# SCH_I2C_Divider_2021-08-28.net
KiCad netlist of a schematic drawn in EasyEDA
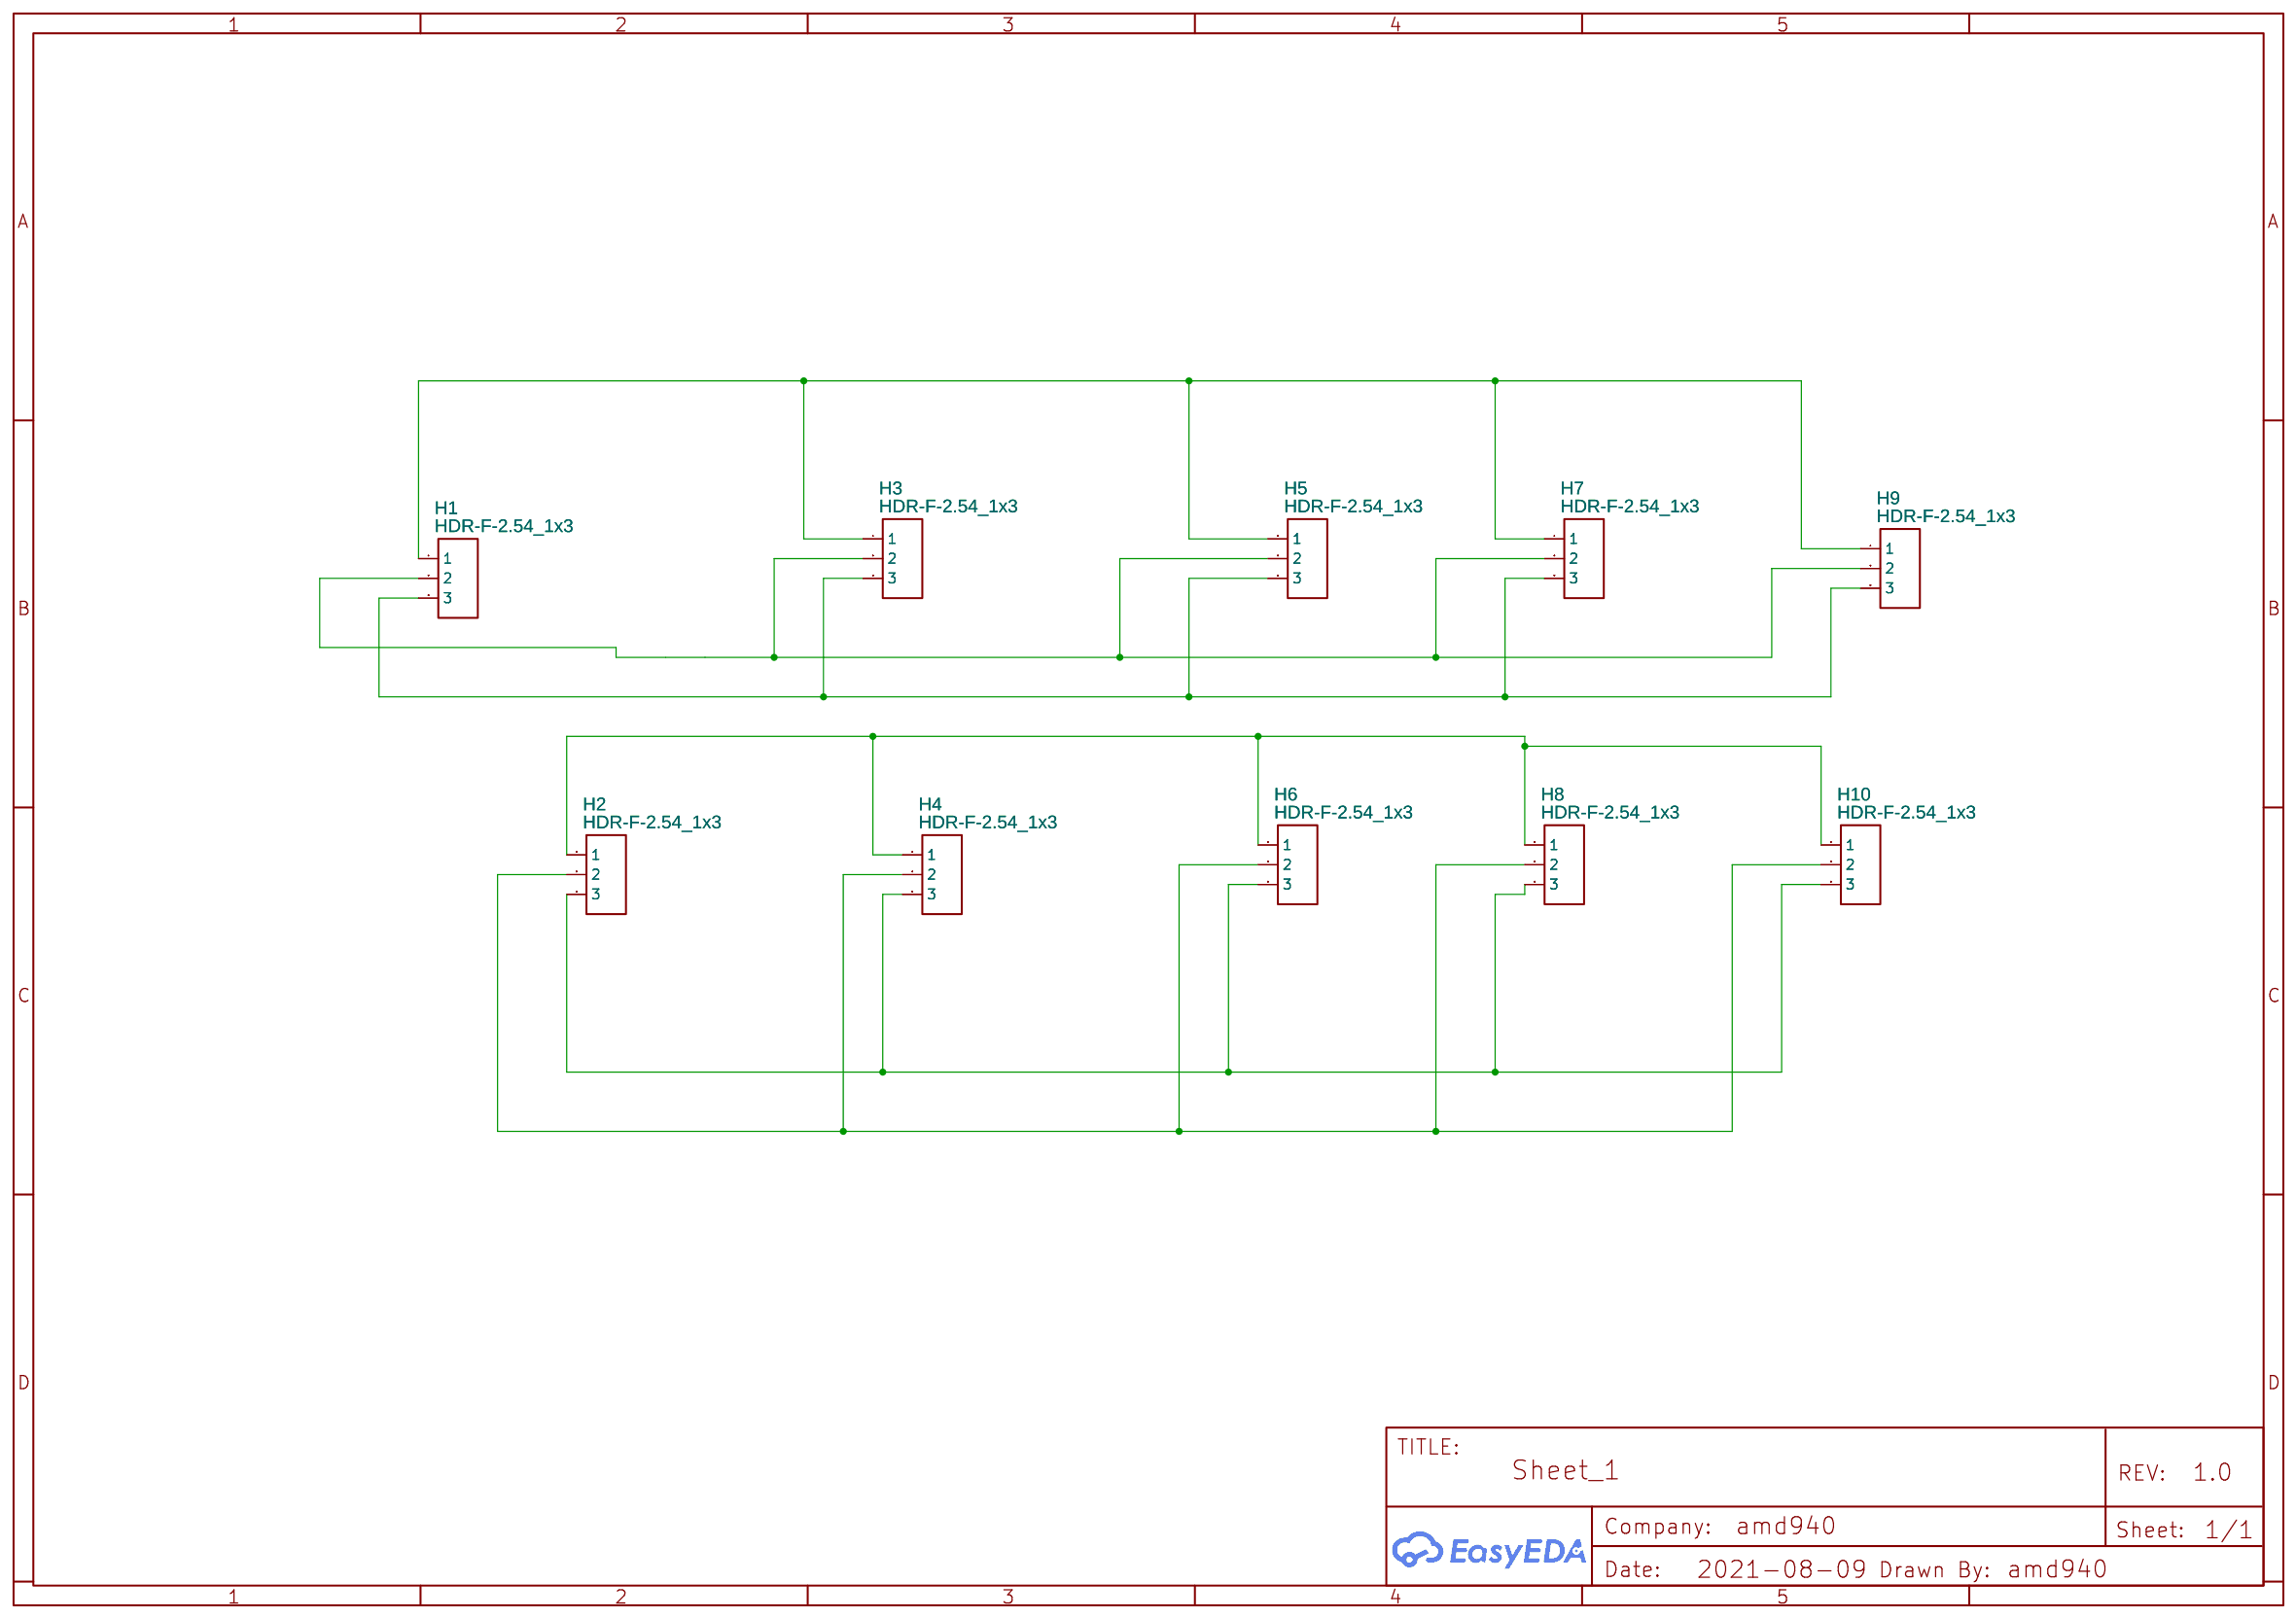
[diagram p0: schematic sheet]

(export (version "E")
  (design (tool "Eeschema 10.0.6"))
  (components
    (comp (ref "H1")
      (value "HDR-F-2.54_1x3")
      (fields (field (name "BOM_Supplier Part") "C146690"))
      (libsource (lib "") (part "HDR-F-2.54_1x3"))
    )
    (comp (ref "H2")
      (value "HDR-F-2.54_1x3")
      (fields (field (name "BOM_Supplier Part") "C146690"))
      (libsource (lib "") (part "HDR-F-2.54_1x3"))
    )
    (comp (ref "H3")
      (value "HDR-F-2.54_1x3")
      (fields (field (name "BOM_Supplier Part") "C146690"))
      (libsource (lib "") (part "HDR-F-2.54_1x3"))
    )
    (comp (ref "H4")
      (value "HDR-F-2.54_1x3")
      (fields (field (name "BOM_Supplier Part") "C146690"))
      (libsource (lib "") (part "HDR-F-2.54_1x3"))
    )
    (comp (ref "H5")
      (value "HDR-F-2.54_1x3")
      (fields (field (name "BOM_Supplier Part") "C146690"))
      (libsource (lib "") (part "HDR-F-2.54_1x3"))
    )
    (comp (ref "H6")
      (value "HDR-F-2.54_1x3")
      (fields (field (name "BOM_Supplier Part") "C146690"))
      (libsource (lib "") (part "HDR-F-2.54_1x3"))
    )
    (comp (ref "H7")
      (value "HDR-F-2.54_1x3")
      (fields (field (name "BOM_Supplier Part") "C146690"))
      (libsource (lib "") (part "HDR-F-2.54_1x3"))
    )
    (comp (ref "H8")
      (value "HDR-F-2.54_1x3")
      (fields (field (name "BOM_Supplier Part") "C146690"))
      (libsource (lib "") (part "HDR-F-2.54_1x3"))
    )
    (comp (ref "H9")
      (value "HDR-F-2.54_1x3")
      (fields (field (name "BOM_Supplier Part") "C146690"))
      (libsource (lib "") (part "HDR-F-2.54_1x3"))
    )
    (comp (ref "H10")
      (value "HDR-F-2.54_1x3")
      (fields (field (name "BOM_Supplier Part") "C146690"))
      (libsource (lib "") (part "HDR-F-2.54_1x3"))
    )
  )
  (nets
    (net (code "1") (name "Net-(H1-Pad1)") (class "Default")
      (node (ref "H1") (pin "1") (pinfunction "1_1") (pintype "input"))
      (node (ref "H3") (pin "1") (pinfunction "1_1") (pintype "input"))
      (node (ref "H5") (pin "1") (pinfunction "1_1") (pintype "input"))
      (node (ref "H7") (pin "1") (pinfunction "1_1") (pintype "input"))
      (node (ref "H9") (pin "1") (pinfunction "1_1") (pintype "input"))
    )
    (net (code "2") (name "Net-(H1-Pad2)") (class "Default")
      (node (ref "H1") (pin "2") (pinfunction "2_2") (pintype "input"))
      (node (ref "H3") (pin "2") (pinfunction "2_2") (pintype "input"))
      (node (ref "H5") (pin "2") (pinfunction "2_2") (pintype "input"))
      (node (ref "H7") (pin "2") (pinfunction "2_2") (pintype "input"))
      (node (ref "H9") (pin "2") (pinfunction "2_2") (pintype "input"))
    )
    (net (code "3") (name "Net-(H1-Pad3)") (class "Default")
      (node (ref "H1") (pin "3") (pinfunction "3_3") (pintype "input"))
      (node (ref "H3") (pin "3") (pinfunction "3_3") (pintype "input"))
      (node (ref "H5") (pin "3") (pinfunction "3_3") (pintype "input"))
      (node (ref "H7") (pin "3") (pinfunction "3_3") (pintype "input"))
      (node (ref "H9") (pin "3") (pinfunction "3_3") (pintype "input"))
    )
    (net (code "4") (name "Net-(H10-Pad1)") (class "Default")
      (node (ref "H10") (pin "1") (pinfunction "1_1") (pintype "input"))
      (node (ref "H2") (pin "1") (pinfunction "1_1") (pintype "input"))
      (node (ref "H4") (pin "1") (pinfunction "1_1") (pintype "input"))
      (node (ref "H6") (pin "1") (pinfunction "1_1") (pintype "input"))
      (node (ref "H8") (pin "1") (pinfunction "1_1") (pintype "input"))
    )
    (net (code "5") (name "Net-(H10-Pad2)") (class "Default")
      (node (ref "H10") (pin "2") (pinfunction "2_2") (pintype "input"))
      (node (ref "H2") (pin "2") (pinfunction "2_2") (pintype "input"))
      (node (ref "H4") (pin "2") (pinfunction "2_2") (pintype "input"))
      (node (ref "H6") (pin "2") (pinfunction "2_2") (pintype "input"))
      (node (ref "H8") (pin "2") (pinfunction "2_2") (pintype "input"))
    )
    (net (code "6") (name "Net-(H10-Pad3)") (class "Default")
      (node (ref "H10") (pin "3") (pinfunction "3_3") (pintype "input"))
      (node (ref "H2") (pin "3") (pinfunction "3_3") (pintype "input"))
      (node (ref "H4") (pin "3") (pinfunction "3_3") (pintype "input"))
      (node (ref "H6") (pin "3") (pinfunction "3_3") (pintype "input"))
      (node (ref "H8") (pin "3") (pinfunction "3_3") (pintype "input"))
    )
  )
)
